# SolarZ.net
KiCad netlist of a schematic drawn in EAGLE
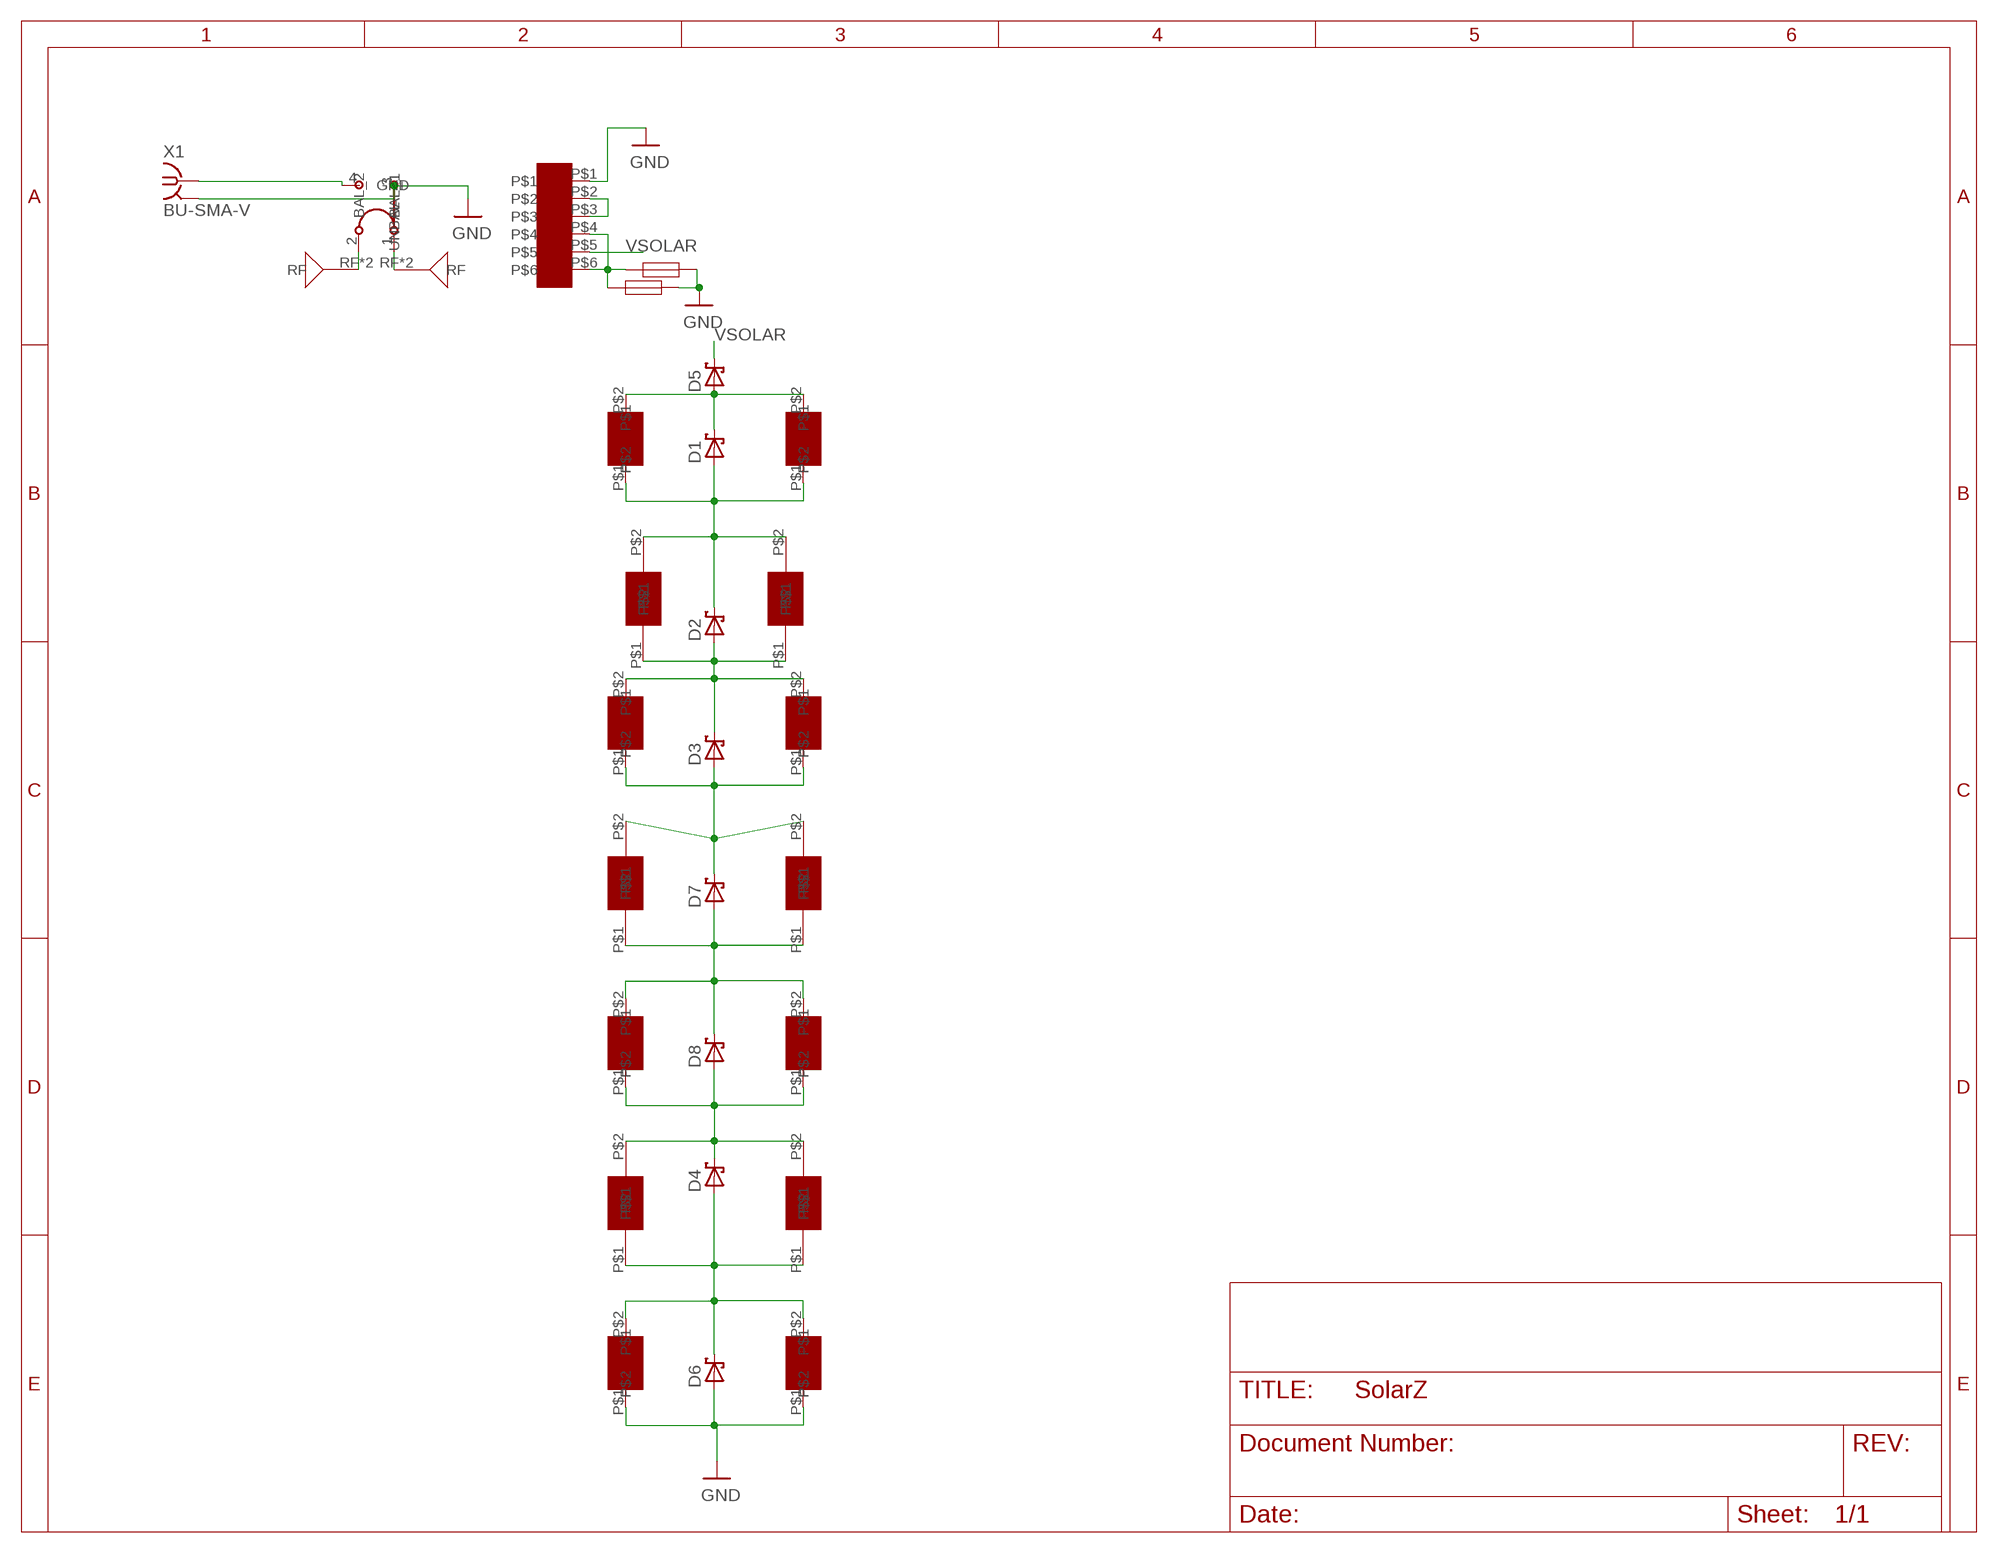
[diagram p0: schematic, sheet 1]

(export (version "E")
  (design (tool "Eeschema 10.0.6"))
  (components
    (comp (ref "1")
      (value "KXOB22-04X3F")
      (footprint "eagle-import:KXOB22-04X3F")
      (libsource (lib "eagle-import") (part "KXOB22-04X3F"))
    )
    (comp (ref "2")
      (value "SLMD121H04L")
      (footprint "eagle-import:SLMD121H04L")
      (libsource (lib "eagle-import") (part "SLMD121H04L"))
    )
    (comp (ref "3")
      (value "SLMD121H04L")
      (footprint "eagle-import:SLMD121H04L")
      (libsource (lib "eagle-import") (part "SLMD121H04L"))
    )
    (comp (ref "4")
      (value "SLMD121H04L")
      (footprint "eagle-import:SLMD121H04L")
      (libsource (lib "eagle-import") (part "SLMD121H04L"))
    )
    (comp (ref "5")
      (value "SLMD121H04L")
      (footprint "eagle-import:SLMD121H04L")
      (libsource (lib "eagle-import") (part "SLMD121H04L"))
    )
    (comp (ref "6")
      (value "KXOB22-04X3F")
      (footprint "eagle-import:KXOB22-04X3F")
      (libsource (lib "eagle-import") (part "KXOB22-04X3F"))
    )
    (comp (ref "7")
      (value "KXOB22-04X3F")
      (footprint "eagle-import:KXOB22-04X3F")
      (libsource (lib "eagle-import") (part "KXOB22-04X3F"))
    )
    (comp (ref "8")
      (value "SLMD121H04L")
      (footprint "eagle-import:SLMD121H04L")
      (libsource (lib "eagle-import") (part "SLMD121H04L"))
    )
    (comp (ref "9")
      (value "SLMD121H04L")
      (footprint "eagle-import:SLMD121H04L")
      (libsource (lib "eagle-import") (part "SLMD121H04L"))
    )
    (comp (ref "10")
      (value "KXOB22-04X3F")
      (footprint "eagle-import:KXOB22-04X3F")
      (libsource (lib "eagle-import") (part "KXOB22-04X3F"))
    )
    (comp (ref "11")
      (value "KXOB22-04X3F")
      (footprint "eagle-import:KXOB22-04X3F")
      (libsource (lib "eagle-import") (part "KXOB22-04X3F"))
    )
    (comp (ref "12")
      (value "SLMD121H04L")
      (footprint "eagle-import:SLMD121H04L")
      (libsource (lib "eagle-import") (part "SLMD121H04L"))
    )
    (comp (ref "13")
      (value "KXOB22-04X3F")
      (footprint "eagle-import:KXOB22-04X3F")
      (libsource (lib "eagle-import") (part "KXOB22-04X3F"))
    )
    (comp (ref "14")
      (value "SLMD121H04L")
      (footprint "eagle-import:SLMD121H04L")
      (libsource (lib "eagle-import") (part "SLMD121H04L"))
    )
    (comp (ref "D1")
      (value "SB_DIODE")
      (footprint "eagle-import:SB_DIODE")
      (libsource (lib "eagle-import") (part "SB_DIODE"))
    )
    (comp (ref "D2")
      (value "SB_DIODE")
      (footprint "eagle-import:SB_DIODE")
      (libsource (lib "eagle-import") (part "SB_DIODE"))
    )
    (comp (ref "D3")
      (value "SB_DIODE")
      (footprint "eagle-import:SB_DIODE")
      (libsource (lib "eagle-import") (part "SB_DIODE"))
    )
    (comp (ref "D4")
      (value "SB_DIODE")
      (footprint "eagle-import:SB_DIODE")
      (libsource (lib "eagle-import") (part "SB_DIODE"))
    )
    (comp (ref "D5")
      (value "SB_DIODE")
      (footprint "eagle-import:SB_DIODE")
      (libsource (lib "eagle-import") (part "SB_DIODE"))
    )
    (comp (ref "D6")
      (value "SB_DIODE")
      (footprint "eagle-import:SB_DIODE")
      (libsource (lib "eagle-import") (part "SB_DIODE"))
    )
    (comp (ref "D7")
      (value "SB_DIODE")
      (footprint "eagle-import:SB_DIODE")
      (libsource (lib "eagle-import") (part "SB_DIODE"))
    )
    (comp (ref "D8")
      (value "SB_DIODE")
      (footprint "eagle-import:SB_DIODE")
      (libsource (lib "eagle-import") (part "SB_DIODE"))
    )
    (comp (ref "F1")
      (value "BURN_TERM")
      (footprint "eagle-import:BURN_WIRE")
      (libsource (lib "eagle-import") (part "BURN_TERM"))
    )
    (comp (ref "F2")
      (value "BURN_TERM")
      (footprint "eagle-import:BURN_WIRE")
      (libsource (lib "eagle-import") (part "BURN_TERM"))
    )
    (comp (ref "U$1")
      (value "BALUN")
      (footprint "eagle-import:BALUN")
      (libsource (lib "eagle-import") (part "BALUN"))
    )
    (comp (ref "U$2")
      (value "ANTENNA")
      (footprint "eagle-import:TAPE")
      (libsource (lib "eagle-import") (part "ANTENNA"))
    )
    (comp (ref "U$3")
      (value "ANTENNA")
      (footprint "eagle-import:TAPE")
      (libsource (lib "eagle-import") (part "ANTENNA"))
    )
    (comp (ref "U$4")
      (value "M20-8760342")
      (footprint "eagle-import:M20-8760342")
      (libsource (lib "eagle-import") (part "M20-8760342"))
    )
    (comp (ref "X1")
      (value "BU-SMA-V")
      (footprint "eagle-import:BU-SMA-V")
      (libsource (lib "eagle-import") (part "BU-SMA-V"))
    )
  )
  (nets
    (net (code "1") (name "/VSOLAR") (class "Default")
      (node (ref "D5") (pin "NEG") (pinfunction "NEG_NEG") (pintype "passive"))
      (node (ref "U$4") (pin "P$5") (pinfunction "P$5_P$5") (pintype "bidirectional"))
    )
    (net (code "2") (name "GND") (class "Default")
      (node (ref "8") (pin "P$1") (pinfunction "P$1_P$1") (pintype "bidirectional"))
      (node (ref "9") (pin "P$1") (pinfunction "P$1_P$1") (pintype "bidirectional"))
      (node (ref "D6") (pin "POS") (pinfunction "POS_POS") (pintype "passive"))
      (node (ref "F1") (pin "2") (pinfunction "2_2") (pintype "bidirectional"))
      (node (ref "F1") (pin "20") (pinfunction "2_20") (pintype "bidirectional"))
      (node (ref "F1") (pin "200") (pinfunction "2_200") (pintype "bidirectional"))
      (node (ref "F2") (pin "2") (pinfunction "2_2") (pintype "bidirectional"))
      (node (ref "F2") (pin "20") (pinfunction "2_20") (pintype "bidirectional"))
      (node (ref "F2") (pin "200") (pinfunction "2_200") (pintype "bidirectional"))
      (node (ref "U$1") (pin "3") (pinfunction "UNBAL_3") (pintype "bidirectional"))
      (node (ref "U$4") (pin "P$1") (pinfunction "P$1_P$1") (pintype "bidirectional"))
      (node (ref "X1") (pin "2") (pinfunction "2_2") (pintype "passive"))
      (node (ref "X1") (pin "3") (pinfunction "2_3") (pintype "passive"))
      (node (ref "X1") (pin "4") (pinfunction "2_4") (pintype "passive"))
      (node (ref "X1") (pin "5") (pinfunction "2_5") (pintype "passive"))
    )
    (net (code "3") (name "Net-(1-PadP$1)") (class "Default")
      (node (ref "1") (pin "P$1") (pinfunction "P$1_P$1") (pintype "bidirectional"))
      (node (ref "13") (pin "P$1") (pinfunction "P$1_P$1") (pintype "bidirectional"))
      (node (ref "4") (pin "P$2") (pinfunction "P$2_P$2") (pintype "bidirectional"))
      (node (ref "5") (pin "P$2") (pinfunction "P$2_P$2") (pintype "bidirectional"))
      (node (ref "D2") (pin "POS") (pinfunction "POS_POS") (pintype "passive"))
      (node (ref "D3") (pin "NEG") (pinfunction "NEG_NEG") (pintype "passive"))
    )
    (net (code "4") (name "Net-(1-PadP$2)") (class "Default")
      (node (ref "1") (pin "P$2") (pinfunction "P$2_P$2") (pintype "bidirectional"))
      (node (ref "13") (pin "P$2") (pinfunction "P$2_P$2") (pintype "bidirectional"))
      (node (ref "2") (pin "P$1") (pinfunction "P$1_P$1") (pintype "bidirectional"))
      (node (ref "3") (pin "P$1") (pinfunction "P$1_P$1") (pintype "bidirectional"))
      (node (ref "D1") (pin "POS") (pinfunction "POS_POS") (pintype "passive"))
      (node (ref "D2") (pin "NEG") (pinfunction "NEG_NEG") (pintype "passive"))
    )
    (net (code "5") (name "Net-(2-PadP$2)") (class "Default")
      (node (ref "2") (pin "P$2") (pinfunction "P$2_P$2") (pintype "bidirectional"))
      (node (ref "3") (pin "P$2") (pinfunction "P$2_P$2") (pintype "bidirectional"))
      (node (ref "D1") (pin "NEG") (pinfunction "NEG_NEG") (pintype "passive"))
      (node (ref "D5") (pin "POS") (pinfunction "POS_POS") (pintype "passive"))
    )
    (net (code "6") (name "Net-(6-PadP$1)") (class "Default")
      (node (ref "6") (pin "P$1") (pinfunction "P$1_P$1") (pintype "bidirectional"))
      (node (ref "7") (pin "P$1") (pinfunction "P$1_P$1") (pintype "bidirectional"))
      (node (ref "8") (pin "P$2") (pinfunction "P$2_P$2") (pintype "bidirectional"))
      (node (ref "9") (pin "P$2") (pinfunction "P$2_P$2") (pintype "bidirectional"))
      (node (ref "D4") (pin "POS") (pinfunction "POS_POS") (pintype "passive"))
      (node (ref "D6") (pin "NEG") (pinfunction "NEG_NEG") (pintype "passive"))
    )
    (net (code "7") (name "Net-(10-PadP$1)") (class "Default")
      (node (ref "10") (pin "P$1") (pinfunction "P$1_P$1") (pintype "bidirectional"))
      (node (ref "11") (pin "P$1") (pinfunction "P$1_P$1") (pintype "bidirectional"))
      (node (ref "12") (pin "P$2") (pinfunction "P$2_P$2") (pintype "bidirectional"))
      (node (ref "14") (pin "P$2") (pinfunction "P$2_P$2") (pintype "bidirectional"))
      (node (ref "D7") (pin "POS") (pinfunction "POS_POS") (pintype "passive"))
      (node (ref "D8") (pin "NEG") (pinfunction "NEG_NEG") (pintype "passive"))
    )
    (net (code "8") (name "Net-(10-PadP$2)") (class "Default")
      (node (ref "10") (pin "P$2") (pinfunction "P$2_P$2") (pintype "bidirectional"))
      (node (ref "11") (pin "P$2") (pinfunction "P$2_P$2") (pintype "bidirectional"))
      (node (ref "4") (pin "P$1") (pinfunction "P$1_P$1") (pintype "bidirectional"))
      (node (ref "5") (pin "P$1") (pinfunction "P$1_P$1") (pintype "bidirectional"))
      (node (ref "D3") (pin "POS") (pinfunction "POS_POS") (pintype "passive"))
      (node (ref "D7") (pin "NEG") (pinfunction "NEG_NEG") (pintype "passive"))
    )
    (net (code "9") (name "Net-(12-PadP$1)") (class "Default")
      (node (ref "12") (pin "P$1") (pinfunction "P$1_P$1") (pintype "bidirectional"))
      (node (ref "14") (pin "P$1") (pinfunction "P$1_P$1") (pintype "bidirectional"))
      (node (ref "6") (pin "P$2") (pinfunction "P$2_P$2") (pintype "bidirectional"))
      (node (ref "7") (pin "P$2") (pinfunction "P$2_P$2") (pintype "bidirectional"))
      (node (ref "D4") (pin "NEG") (pinfunction "NEG_NEG") (pintype "passive"))
      (node (ref "D8") (pin "POS") (pinfunction "POS_POS") (pintype "passive"))
    )
    (net (code "10") (name "Net-(F1-1-Pad10)") (class "Default")
      (node (ref "F1") (pin "1") (pinfunction "1_1") (pintype "bidirectional"))
      (node (ref "F1") (pin "10") (pinfunction "1_10") (pintype "bidirectional"))
      (node (ref "F1") (pin "100") (pinfunction "1_100") (pintype "bidirectional"))
      (node (ref "F2") (pin "1") (pinfunction "1_1") (pintype "bidirectional"))
      (node (ref "F2") (pin "10") (pinfunction "1_10") (pintype "bidirectional"))
      (node (ref "F2") (pin "100") (pinfunction "1_100") (pintype "bidirectional"))
      (node (ref "U$4") (pin "P$4") (pinfunction "P$4_P$4") (pintype "bidirectional"))
      (node (ref "U$4") (pin "P$6") (pinfunction "P$6_P$6") (pintype "bidirectional"))
    )
    (net (code "11") (name "Net-(U$1-BAL_1)") (class "Default")
      (node (ref "U$1") (pin "1") (pinfunction "BAL_1_1") (pintype "input"))
      (node (ref "U$2") (pin "RF") (pinfunction "RF_RF") (pintype "bidirectional"))
      (node (ref "U$2") (pin "RF_2") (pinfunction "RF_RF_2") (pintype "bidirectional"))
    )
    (net (code "12") (name "Net-(U$1-BAL_2)") (class "Default")
      (node (ref "U$1") (pin "2") (pinfunction "BAL_2_2") (pintype "input"))
      (node (ref "U$3") (pin "RF") (pinfunction "RF_RF") (pintype "bidirectional"))
      (node (ref "U$3") (pin "RF_2") (pinfunction "RF_RF_2") (pintype "bidirectional"))
    )
    (net (code "13") (name "Net-(U$1-GND)") (class "Default")
      (node (ref "U$1") (pin "4") (pinfunction "GND_4") (pintype "bidirectional"))
      (node (ref "X1") (pin "1") (pinfunction "1_1") (pintype "passive"))
    )
    (net (code "14") (name "Net-(U$4-PadP$2)") (class "Default")
      (node (ref "U$4") (pin "P$2") (pinfunction "P$2_P$2") (pintype "bidirectional"))
      (node (ref "U$4") (pin "P$3") (pinfunction "P$3_P$3") (pintype "bidirectional"))
    )
  )
)
